# 08_-_CPU_-_SPI_I2C_SD_MMC.net
KiCad netlist of a schematic drawn in Altium Designer
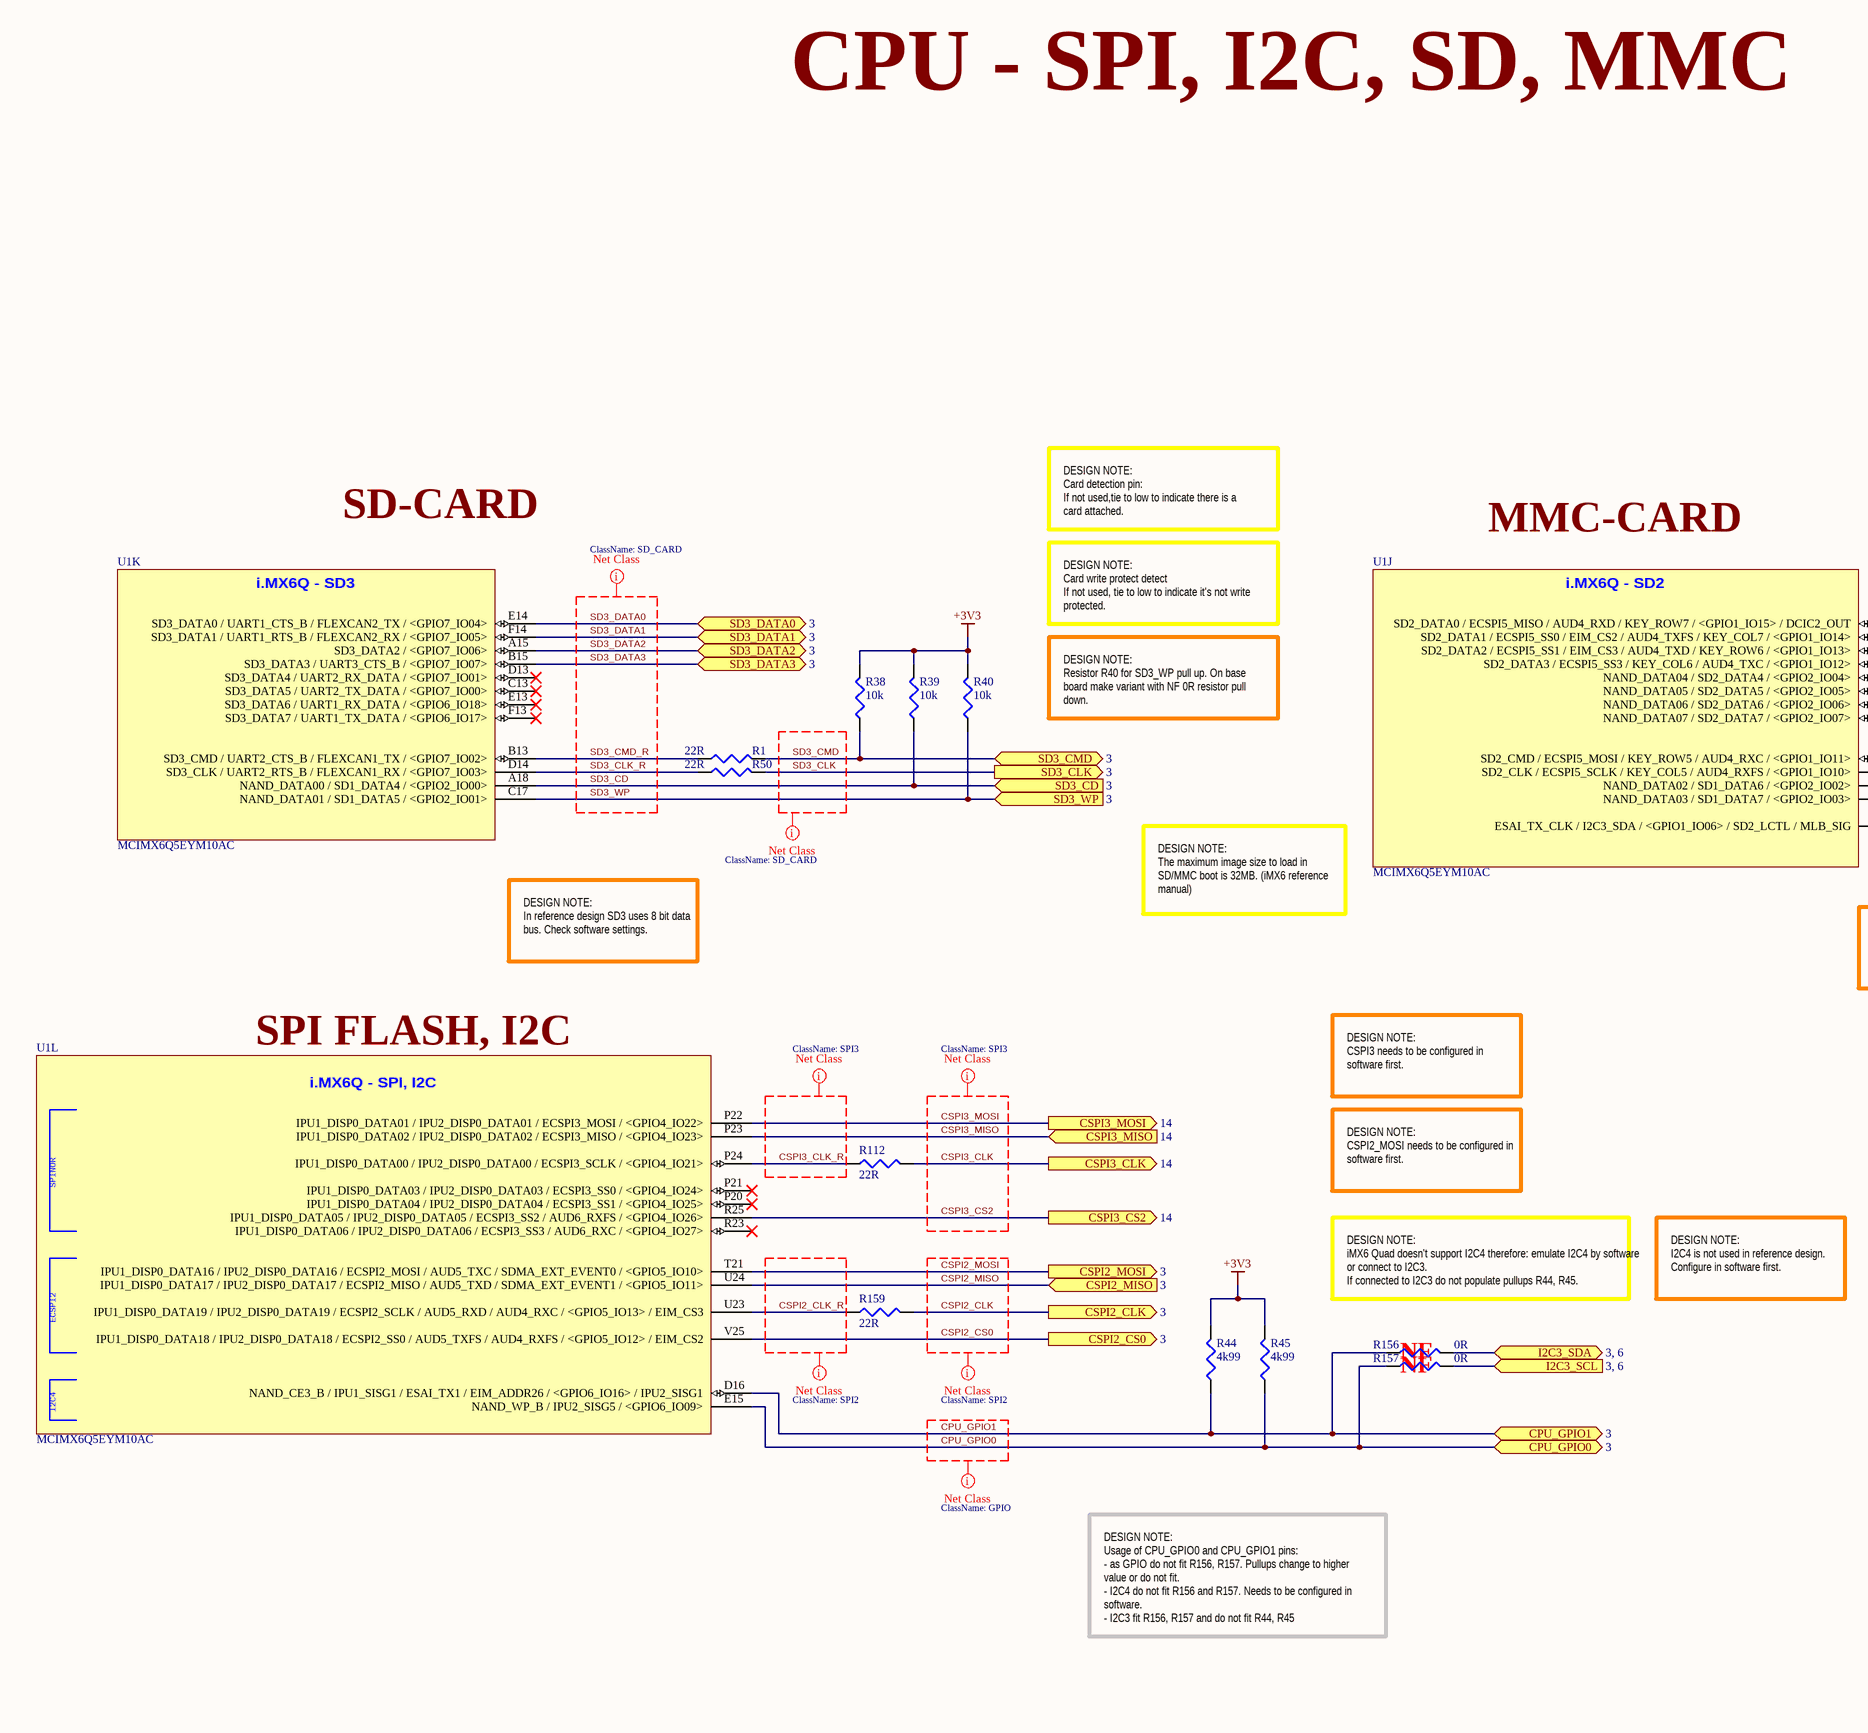
[diagram p0: [08] - CPU - SPI, I2C, SD, MMC.SchDoc, left]
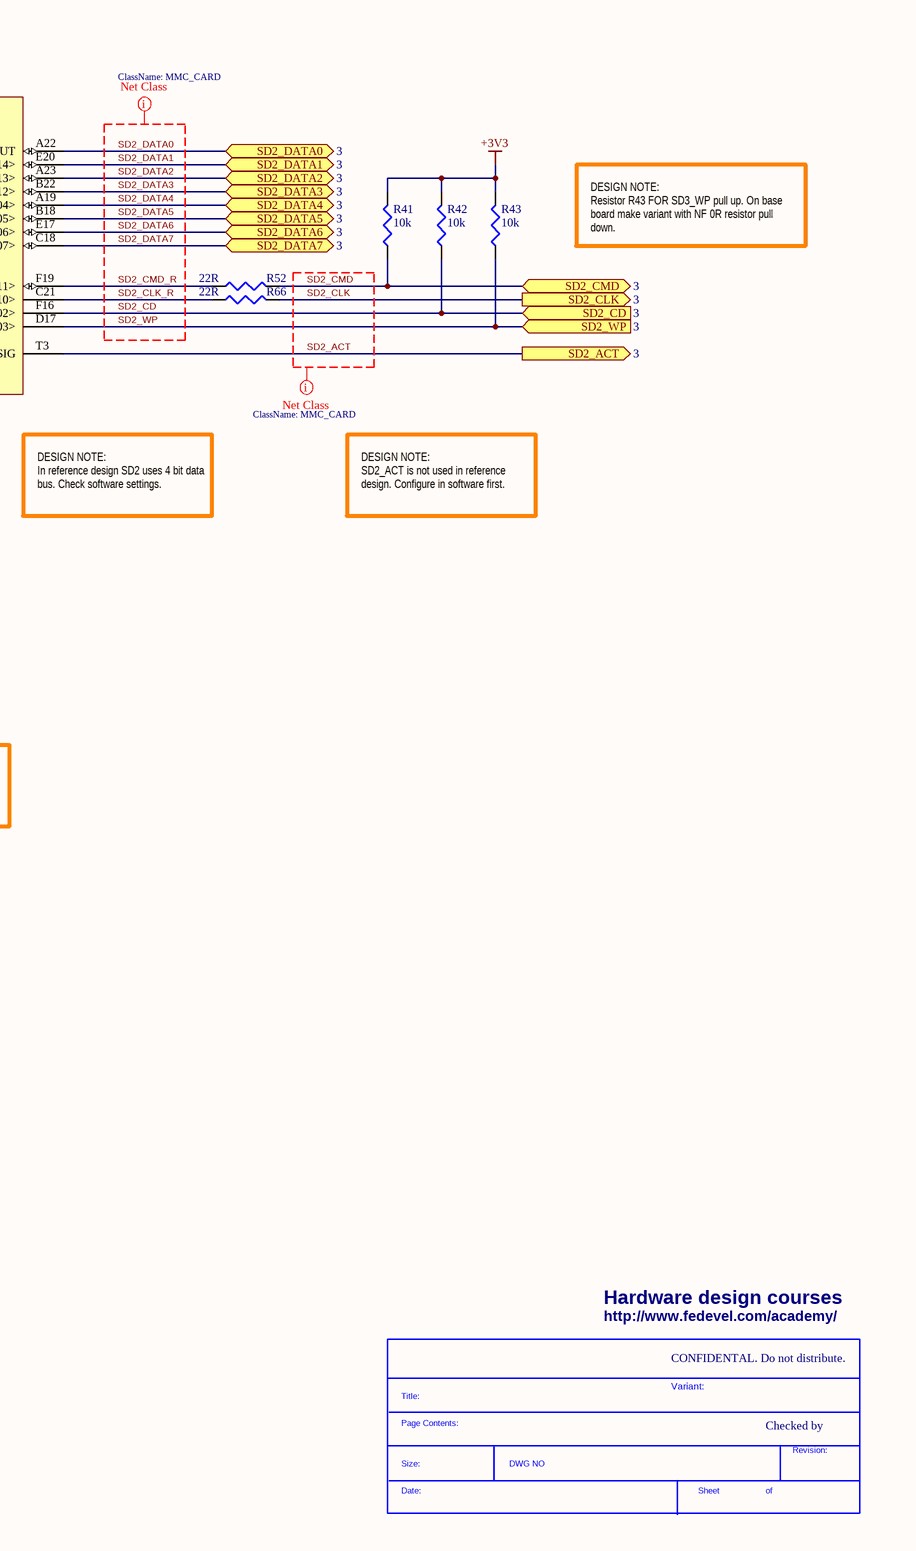
[diagram p1: [08] - CPU - SPI, I2C, SD, MMC.SchDoc, right]

(export (version "E")
  (design (tool "Eeschema 10.0.6"))
  (components
    (comp (ref "R1")
      (value "22R")
      (footprint "R0402")
      (description "RES 22.0 OHM 1/16W 1% 0402 SMD")
      (fields
        (field (name "MANUFACTURER") "Yageo")
        (field (name "MANUFACTURER PART NUMBER") "RC0402FR-0722RL")
      )
      (libsource (lib "Integrated_Library_RF_FEB_2012") (part "RC0402FR-0722RL"))
    )
    (comp (ref "R38")
      (value "10k")
      (footprint "R0402")
      (description "RES 10.0K OHM 1/16W 1% 0402 SMD")
      (fields
        (field (name "MANUFACTURER") "Yageo")
        (field (name "MANUFACTURER PART NUMBER") "RC0402FR-0710KL")
      )
      (libsource (lib "Integrated_Library_RF_FEB_2012") (part "RC0402FR-0710KL"))
    )
    (comp (ref "R39")
      (value "10k")
      (footprint "R0402")
      (description "RES 10.0K OHM 1/16W 1% 0402 SMD")
      (fields
        (field (name "MANUFACTURER") "Yageo")
        (field (name "MANUFACTURER PART NUMBER") "RC0402FR-0710KL")
      )
      (libsource (lib "Integrated_Library_RF_FEB_2012") (part "RC0402FR-0710KL"))
    )
    (comp (ref "R40")
      (value "10k")
      (footprint "R0402")
      (description "RES 10.0K OHM 1/16W 1% 0402 SMD")
      (fields
        (field (name "MANUFACTURER") "Yageo")
        (field (name "MANUFACTURER PART NUMBER") "RC0402FR-0710KL")
      )
      (libsource (lib "Integrated_Library_RF_FEB_2012") (part "RC0402FR-0710KL"))
    )
    (comp (ref "R41")
      (value "10k")
      (footprint "R0402")
      (description "RES 10.0K OHM 1/16W 1% 0402 SMD")
      (fields
        (field (name "MANUFACTURER") "Yageo")
        (field (name "MANUFACTURER PART NUMBER") "RC0402FR-0710KL")
      )
      (libsource (lib "Integrated_Library_RF_FEB_2012") (part "RC0402FR-0710KL"))
    )
    (comp (ref "R42")
      (value "10k")
      (footprint "R0402")
      (description "RES 10.0K OHM 1/16W 1% 0402 SMD")
      (fields
        (field (name "MANUFACTURER") "Yageo")
        (field (name "MANUFACTURER PART NUMBER") "RC0402FR-0710KL")
      )
      (libsource (lib "Integrated_Library_RF_FEB_2012") (part "RC0402FR-0710KL"))
    )
    (comp (ref "R43")
      (value "10k")
      (footprint "R0402")
      (description "RES 10.0K OHM 1/16W 1% 0402 SMD")
      (fields
        (field (name "MANUFACTURER") "Yageo")
        (field (name "MANUFACTURER PART NUMBER") "RC0402FR-0710KL")
      )
      (libsource (lib "Integrated_Library_RF_FEB_2012") (part "RC0402FR-0710KL"))
    )
    (comp (ref "R44")
      (value "4k99")
      (footprint "R0402")
      (description "RES TF 4.99K OHM 1% 1/16W 0402")
      (fields
        (field (name "MANUFACTURER") "Stackpole Electronics Inc")
        (field (name "MANUFACTURER PART NUMBER") "RMCF0402FT4K99")
      )
      (libsource (lib "Integrated_Library_RF_FEB_2012") (part "RMCF0402FT4K99"))
    )
    (comp (ref "R45")
      (value "4k99")
      (footprint "R0402")
      (description "RES TF 4.99K OHM 1% 1/16W 0402")
      (fields
        (field (name "MANUFACTURER") "Stackpole Electronics Inc")
        (field (name "MANUFACTURER PART NUMBER") "RMCF0402FT4K99")
      )
      (libsource (lib "Integrated_Library_RF_FEB_2012") (part "RMCF0402FT4K99"))
    )
    (comp (ref "R50")
      (value "22R")
      (footprint "R0402")
      (description "RES 22.0 OHM 1/16W 1% 0402 SMD")
      (fields
        (field (name "MANUFACTURER") "Yageo")
        (field (name "MANUFACTURER PART NUMBER") "RC0402FR-0722RL")
      )
      (libsource (lib "Integrated_Library_RF_FEB_2012") (part "RC0402FR-0722RL"))
    )
    (comp (ref "R52")
      (value "22R")
      (footprint "R0402")
      (description "RES 22.0 OHM 1/16W 1% 0402 SMD")
      (fields
        (field (name "MANUFACTURER") "Yageo")
        (field (name "MANUFACTURER PART NUMBER") "RC0402FR-0722RL")
      )
      (libsource (lib "Integrated_Library_RF_FEB_2012") (part "RC0402FR-0722RL"))
    )
    (comp (ref "R66")
      (value "22R")
      (footprint "R0402")
      (description "RES 22.0 OHM 1/16W 1% 0402 SMD")
      (fields
        (field (name "MANUFACTURER") "Yageo")
        (field (name "MANUFACTURER PART NUMBER") "RC0402FR-0722RL")
      )
      (libsource (lib "Integrated_Library_RF_FEB_2012") (part "RC0402FR-0722RL"))
    )
    (comp (ref "R112")
      (value "22R")
      (footprint "R0402")
      (description "RES 22.0 OHM 1/16W 1% 0402 SMD")
      (fields
        (field (name "MANUFACTURER") "Yageo")
        (field (name "MANUFACTURER PART NUMBER") "RC0402FR-0722RL")
      )
      (libsource (lib "Integrated_Library_RF_FEB_2012") (part "RC0402FR-0722RL"))
    )
    (comp (ref "R156")
      (value "0R")
      (footprint "R0402")
      (description "RES 0.0 OHM 1/16W 0402 SMD")
      (fields
        (field (name "MANUFACTURER") "Yageo")
        (field (name "MANUFACTURER PART NUMBER") "RC0402JR-070RL")
      )
      (libsource (lib "Integrated_Library_RF_FEB_2012") (part "RC0402JR-070RL"))
    )
    (comp (ref "R157")
      (value "0R")
      (footprint "R0402")
      (description "RES 0.0 OHM 1/16W 0402 SMD")
      (fields
        (field (name "MANUFACTURER") "Yageo")
        (field (name "MANUFACTURER PART NUMBER") "RC0402JR-070RL")
      )
      (libsource (lib "Integrated_Library_RF_FEB_2012") (part "RC0402JR-070RL"))
    )
    (comp (ref "R159")
      (value "22R")
      (footprint "R0402")
      (description "RES 22.0 OHM 1/16W 1% 0402 SMD")
      (fields
        (field (name "MANUFACTURER") "Yageo")
        (field (name "MANUFACTURER PART NUMBER") "RC0402FR-0722RL")
      )
      (libsource (lib "Integrated_Library_RF_FEB_2012") (part "RC0402FR-0722RL"))
    )
    (comp (ref "U1")
      (value "MCIMX6Q5EYM10AC")
      (footprint "PBGA624")
      (description "IC MCU 32BIT ARM QUAD 624FCBGA")
      (fields
        (field (name "MANUFACTURER") "Freescale Semiconductor")
        (field (name ".CREATOR") "MM")
        (field (name ".CHECKED PCB") "MM, checked by RF")
        (field (name ".CHECKED SCH") "MM")
      )
      (libsource (lib "Schlib_RF") (part "MCIMX6Q5EYM10AC"))
    )
  )
  (nets
    (net (code "1") (name "+3V3") (class "Default")
      (node (ref "R38") (pin "2") (pinfunction "2_2") (pintype "passive"))
      (node (ref "R39") (pin "2") (pinfunction "2_2") (pintype "passive"))
      (node (ref "R40") (pin "2") (pinfunction "2_2") (pintype "passive"))
      (node (ref "R41") (pin "2") (pinfunction "2_2") (pintype "passive"))
      (node (ref "R42") (pin "2") (pinfunction "2_2") (pintype "passive"))
      (node (ref "R43") (pin "2") (pinfunction "2_2") (pintype "passive"))
      (node (ref "R44") (pin "2") (pinfunction "2_2") (pintype "passive"))
      (node (ref "R45") (pin "2") (pinfunction "2_2") (pintype "passive"))
    )
    (net (code "2") (name "/CPU_GPIO0") (class "Default")
      (node (ref "R157") (pin "1") (pinfunction "1_1") (pintype "passive"))
      (node (ref "R45") (pin "1") (pinfunction "1_1") (pintype "passive"))
      (node (ref "U1") (pin "E15") (pinfunction "NAND_WP_B_/_IPU2_SISG5_/_<GPIO6_IO09>_E15") (pintype "passive"))
    )
    (net (code "3") (name "/CPU_GPIO1") (class "Default")
      (node (ref "R156") (pin "1") (pinfunction "1_1") (pintype "passive"))
      (node (ref "R44") (pin "1") (pinfunction "1_1") (pintype "passive"))
      (node (ref "U1") (pin "D16") (pinfunction "NAND_CE3_B_/_IPU1_SISG1_/_ESAI_TX1_/_EIM_ADDR26_/_<GPIO6_IO16>_/_IPU2_SISG1_D16") (pintype "bidirectional"))
    )
    (net (code "4") (name "/CSPI2_CLK") (class "Default")
      (node (ref "R159") (pin "2") (pinfunction "2_2") (pintype "passive"))
    )
    (net (code "5") (name "/CSPI2_CLK_R") (class "Default")
      (node (ref "R159") (pin "1") (pinfunction "1_1") (pintype "passive"))
      (node (ref "U1") (pin "U23") (pinfunction "IPU1_DISP0_DATA19_/_IPU2_DISP0_DATA19_/_ECSPI2_SCLK_/_AUD5_RXD_/_AUD4_RXC_/_<GPIO5_IO13>_/_EIM_CS3_U23") (pintype "passive"))
    )
    (net (code "6") (name "/CSPI2_CS0") (class "Default")
      (node (ref "U1") (pin "V25") (pinfunction "IPU1_DISP0_DATA18_/_IPU2_DISP0_DATA18_/_ECSPI2_SS0_/_AUD5_TXFS_/_AUD4_RXFS_/_<GPIO5_IO12>_/_EIM_CS2_V25") (pintype "passive"))
    )
    (net (code "7") (name "/CSPI2_MISO") (class "Default")
      (node (ref "U1") (pin "U24") (pinfunction "IPU1_DISP0_DATA17_/_IPU2_DISP0_DATA17_/_ECSPI2_MISO_/_AUD5_TXD_/_SDMA_EXT_EVENT1_/_<GPIO5_IO11>_U24") (pintype "passive"))
    )
    (net (code "8") (name "/CSPI2_MOSI") (class "Default")
      (node (ref "U1") (pin "T21") (pinfunction "IPU1_DISP0_DATA16_/_IPU2_DISP0_DATA16_/_ECSPI2_MOSI_/_AUD5_TXC_/_SDMA_EXT_EVENT0_/_<GPIO5_IO10>_T21") (pintype "passive"))
    )
    (net (code "9") (name "/CSPI3_CLK") (class "Default")
      (node (ref "R112") (pin "2") (pinfunction "2_2") (pintype "passive"))
    )
    (net (code "10") (name "/CSPI3_CLK_R") (class "Default")
      (node (ref "R112") (pin "1") (pinfunction "1_1") (pintype "passive"))
      (node (ref "U1") (pin "P24") (pinfunction "IPU1_DISP0_DATA00_/_IPU2_DISP0_DATA00_/_ECSPI3_SCLK_/_<GPIO4_IO21>_P24") (pintype "bidirectional"))
    )
    (net (code "11") (name "/CSPI3_CS2") (class "Default")
      (node (ref "U1") (pin "R25") (pinfunction "IPU1_DISP0_DATA05_/_IPU2_DISP0_DATA05_/_ECSPI3_SS2_/_AUD6_RXFS_/_<GPIO4_IO26>_R25") (pintype "passive"))
    )
    (net (code "12") (name "/CSPI3_MISO") (class "Default")
      (node (ref "U1") (pin "P23") (pinfunction "IPU1_DISP0_DATA02_/_IPU2_DISP0_DATA02_/_ECSPI3_MISO_/_<GPIO4_IO23>_P23") (pintype "passive"))
    )
    (net (code "13") (name "/CSPI3_MOSI") (class "Default")
      (node (ref "U1") (pin "P22") (pinfunction "IPU1_DISP0_DATA01_/_IPU2_DISP0_DATA01_/_ECSPI3_MOSI_/_<GPIO4_IO22>_P22") (pintype "passive"))
    )
    (net (code "14") (name "/I2C3_SCL") (class "Default")
      (node (ref "R157") (pin "2") (pinfunction "2_2") (pintype "passive"))
    )
    (net (code "15") (name "/I2C3_SDA") (class "Default")
      (node (ref "R156") (pin "2") (pinfunction "2_2") (pintype "passive"))
    )
    (net (code "16") (name "/SD2_ACT") (class "Default")
      (node (ref "U1") (pin "T3") (pinfunction "ESAI_TX_CLK_/_I2C3_SDA_/_<GPIO1_IO06>_/_SD2_LCTL_/_MLB_SIG_T3") (pintype "passive"))
    )
    (net (code "17") (name "/SD2_CD") (class "Default")
      (node (ref "R42") (pin "1") (pinfunction "1_1") (pintype "passive"))
      (node (ref "U1") (pin "F16") (pinfunction "NAND_DATA02_/_SD1_DATA6_/_<GPIO2_IO02>_F16") (pintype "passive"))
    )
    (net (code "18") (name "/SD2_CLK") (class "Default")
      (node (ref "R66") (pin "2") (pinfunction "2_2") (pintype "passive"))
    )
    (net (code "19") (name "/SD2_CLK_R") (class "Default")
      (node (ref "R66") (pin "1") (pinfunction "1_1") (pintype "passive"))
      (node (ref "U1") (pin "C21") (pinfunction "SD2_CLK_/_ECSPI5_SCLK_/_KEY_COL5_/_AUD4_RXFS_/_<GPIO1_IO10>_C21") (pintype "passive"))
    )
    (net (code "20") (name "/SD2_CMD") (class "Default")
      (node (ref "R41") (pin "1") (pinfunction "1_1") (pintype "passive"))
      (node (ref "R52") (pin "2") (pinfunction "2_2") (pintype "passive"))
    )
    (net (code "21") (name "/SD2_CMD_R") (class "Default")
      (node (ref "R52") (pin "1") (pinfunction "1_1") (pintype "passive"))
      (node (ref "U1") (pin "F19") (pinfunction "SD2_CMD_/_ECSPI5_MOSI_/_KEY_ROW5_/_AUD4_RXC_/_<GPIO1_IO11>_F19") (pintype "bidirectional"))
    )
    (net (code "22") (name "/SD2_DATA0") (class "Default")
      (node (ref "U1") (pin "A22") (pinfunction "SD2_DATA0_/_ECSPI5_MISO_/_AUD4_RXD_/_KEY_ROW7_/_<GPIO1_IO15>_/_DCIC2_OUT_A22") (pintype "bidirectional"))
    )
    (net (code "23") (name "/SD2_DATA1") (class "Default")
      (node (ref "U1") (pin "E20") (pinfunction "SD2_DATA1_/_ECSPI5_SS0_/_EIM_CS2_/_AUD4_TXFS_/_KEY_COL7_/_<GPIO1_IO14>_E20") (pintype "bidirectional"))
    )
    (net (code "24") (name "/SD2_DATA2") (class "Default")
      (node (ref "U1") (pin "A23") (pinfunction "SD2_DATA2_/_ECSPI5_SS1_/_EIM_CS3_/_AUD4_TXD_/_KEY_ROW6_/_<GPIO1_IO13>_A23") (pintype "bidirectional"))
    )
    (net (code "25") (name "/SD2_DATA3") (class "Default")
      (node (ref "U1") (pin "B22") (pinfunction "SD2_DATA3_/_ECSPI5_SS3_/_KEY_COL6_/_AUD4_TXC_/_<GPIO1_IO12>_B22") (pintype "bidirectional"))
    )
    (net (code "26") (name "/SD2_DATA4") (class "Default")
      (node (ref "U1") (pin "A19") (pinfunction "NAND_DATA04_/_SD2_DATA4_/_<GPIO2_IO04>_A19") (pintype "bidirectional"))
    )
    (net (code "27") (name "/SD2_DATA5") (class "Default")
      (node (ref "U1") (pin "B18") (pinfunction "NAND_DATA05_/_SD2_DATA5_/_<GPIO2_IO05>_B18") (pintype "bidirectional"))
    )
    (net (code "28") (name "/SD2_DATA6") (class "Default")
      (node (ref "U1") (pin "E17") (pinfunction "NAND_DATA06_/_SD2_DATA6_/_<GPIO2_IO06>_E17") (pintype "bidirectional"))
    )
    (net (code "29") (name "/SD2_DATA7") (class "Default")
      (node (ref "U1") (pin "C18") (pinfunction "NAND_DATA07_/_SD2_DATA7_/_<GPIO2_IO07>_C18") (pintype "bidirectional"))
    )
    (net (code "30") (name "/SD2_WP") (class "Default")
      (node (ref "R43") (pin "1") (pinfunction "1_1") (pintype "passive"))
      (node (ref "U1") (pin "D17") (pinfunction "NAND_DATA03_/_SD1_DATA7_/_<GPIO2_IO03>_D17") (pintype "passive"))
    )
    (net (code "31") (name "/SD3_CD") (class "Default")
      (node (ref "R39") (pin "1") (pinfunction "1_1") (pintype "passive"))
      (node (ref "U1") (pin "A18") (pinfunction "NAND_DATA00_/_SD1_DATA4_/_<GPIO2_IO00>_A18") (pintype "passive"))
    )
    (net (code "32") (name "/SD3_CLK") (class "Default")
      (node (ref "R50") (pin "2") (pinfunction "2_2") (pintype "passive"))
    )
    (net (code "33") (name "/SD3_CLK_R") (class "Default")
      (node (ref "R50") (pin "1") (pinfunction "1_1") (pintype "passive"))
      (node (ref "U1") (pin "D14") (pinfunction "SD3_CLK_/_UART2_RTS_B_/_FLEXCAN1_RX_/_<GPIO7_IO03>_D14") (pintype "passive"))
    )
    (net (code "34") (name "/SD3_CMD") (class "Default")
      (node (ref "R1") (pin "2") (pinfunction "2_2") (pintype "passive"))
      (node (ref "R38") (pin "1") (pinfunction "1_1") (pintype "passive"))
    )
    (net (code "35") (name "/SD3_CMD_R") (class "Default")
      (node (ref "R1") (pin "1") (pinfunction "1_1") (pintype "passive"))
      (node (ref "U1") (pin "B13") (pinfunction "SD3_CMD_/_UART2_CTS_B_/_FLEXCAN1_TX_/_<GPIO7_IO02>_B13") (pintype "bidirectional"))
    )
    (net (code "36") (name "/SD3_DATA0") (class "Default")
      (node (ref "U1") (pin "E14") (pinfunction "SD3_DATA0_/_UART1_CTS_B_/_FLEXCAN2_TX_/_<GPIO7_IO04>_E14") (pintype "bidirectional"))
    )
    (net (code "37") (name "/SD3_DATA1") (class "Default")
      (node (ref "U1") (pin "F14") (pinfunction "SD3_DATA1_/_UART1_RTS_B_/_FLEXCAN2_RX_/_<GPIO7_IO05>_F14") (pintype "bidirectional"))
    )
    (net (code "38") (name "/SD3_DATA2") (class "Default")
      (node (ref "U1") (pin "A15") (pinfunction "SD3_DATA2_/_<GPIO7_IO06>_A15") (pintype "bidirectional"))
    )
    (net (code "39") (name "/SD3_DATA3") (class "Default")
      (node (ref "U1") (pin "B15") (pinfunction "SD3_DATA3_/_UART3_CTS_B_/_<GPIO7_IO07>_B15") (pintype "bidirectional"))
    )
    (net (code "40") (name "/SD3_WP") (class "Default")
      (node (ref "R40") (pin "1") (pinfunction "1_1") (pintype "passive"))
      (node (ref "U1") (pin "C17") (pinfunction "NAND_DATA01_/_SD1_DATA5_/_<GPIO2_IO01>_C17") (pintype "passive"))
    )
    (net (code "41") (name "unconnected-(U1K-SD3_DATA4_{slash}_UART2_RX_DATA_{slash}_<GPIO7_IO01>-PadD13)") (class "Default")
      (node (ref "U1") (pin "D13") (pinfunction "SD3_DATA4_/_UART2_RX_DATA_/_<GPIO7_IO01>_D13") (pintype "bidirectional+no_connect"))
    )
    (net (code "42") (name "unconnected-(U1K-SD3_DATA5_{slash}_UART2_TX_DATA_{slash}_<GPIO7_IO00>-PadC13)") (class "Default")
      (node (ref "U1") (pin "C13") (pinfunction "SD3_DATA5_/_UART2_TX_DATA_/_<GPIO7_IO00>_C13") (pintype "bidirectional+no_connect"))
    )
    (net (code "43") (name "unconnected-(U1K-SD3_DATA6_{slash}_UART1_RX_DATA_{slash}_<GPIO6_IO18>-PadE13)") (class "Default")
      (node (ref "U1") (pin "E13") (pinfunction "SD3_DATA6_/_UART1_RX_DATA_/_<GPIO6_IO18>_E13") (pintype "bidirectional+no_connect"))
    )
    (net (code "44") (name "unconnected-(U1K-SD3_DATA7_{slash}_UART1_TX_DATA_{slash}_<GPIO6_IO17>-PadF13)") (class "Default")
      (node (ref "U1") (pin "F13") (pinfunction "SD3_DATA7_/_UART1_TX_DATA_/_<GPIO6_IO17>_F13") (pintype "bidirectional+no_connect"))
    )
    (net (code "45") (name "unconnected-(U1L-IPU1_DISP0_DATA03_{slash}_IPU2_DISP0_DATA03_{slash}_ECSPI3_SS0_{slash}_<GPIO4_IO24>-PadP21)") (class "Default")
      (node (ref "U1") (pin "P21") (pinfunction "IPU1_DISP0_DATA03_/_IPU2_DISP0_DATA03_/_ECSPI3_SS0_/_<GPIO4_IO24>_P21") (pintype "bidirectional+no_connect"))
    )
    (net (code "46") (name "unconnected-(U1L-IPU1_DISP0_DATA04_{slash}_IPU2_DISP0_DATA04_{slash}_ECSPI3_SS1_{slash}_<GPIO4_IO25>-PadP20)") (class "Default")
      (node (ref "U1") (pin "P20") (pinfunction "IPU1_DISP0_DATA04_/_IPU2_DISP0_DATA04_/_ECSPI3_SS1_/_<GPIO4_IO25>_P20") (pintype "bidirectional+no_connect"))
    )
    (net (code "47") (name "unconnected-(U1L-IPU1_DISP0_DATA06_{slash}_IPU2_DISP0_DATA06_{slash}_ECSPI3_SS3_{slash}_AUD6_RXC_{slash}_<GPIO4_IO27>-PadR23)") (class "Default")
      (node (ref "U1") (pin "R23") (pinfunction "IPU1_DISP0_DATA06_/_IPU2_DISP0_DATA06_/_ECSPI3_SS3_/_AUD6_RXC_/_<GPIO4_IO27>_R23") (pintype "bidirectional+no_connect"))
    )
  )
)
